# 12V_Rail.net
KiCad netlist of a schematic drawn in Altium Designer
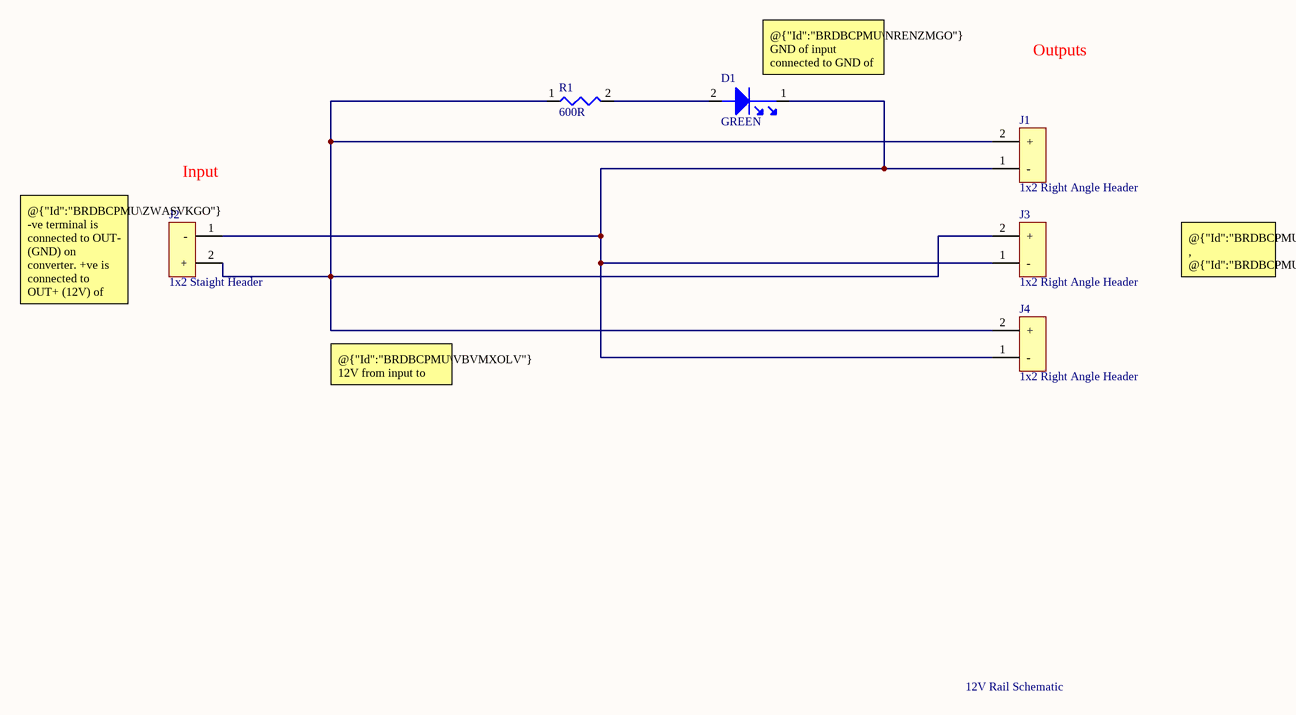
[diagram p0: 12V Rail.SchDoc]

(export (version "E")
  (design (tool "Eeschema 10.0.6"))
  (components
    (comp (ref "D1")
      (value "GREEN")
      (footprint "LED")
      (description "Green T-1 3/4 5 mm 20° Tinted 80 mcd 2.2 V Solid State LED Lamp Through Hole")
      (fields (field (name "MANUFACTURER") "Kingbright") (field (name "MANUFACTURER PART NUMBER") "WP7113GT"))
      (libsource (lib "VR Interface SchLib") (part "WP7113GT"))
    )
    (comp (ref "J1")
      (value "1x2 Right Angle Header")
      (footprint "39291028 Molex Output")
      (description "Connector Wire to Board Header 2 Position 4.2mm Solder Right Angle Thru-Hole Tray")
      (fields (field (name "MANUFACTURER") "Molex") (field (name "MANUFACTURER PART NUMBER") "39-29-1028"))
      (libsource (lib "VR Interface SchLib") (part "39-29-1028"))
    )
    (comp (ref "J2")
      (value "1x2 Staight Header")
      (footprint "39281023 Molex Input")
      (description "Connector Wire to Board Header 2 Position 4.2mm Solder Straight Thru-Hole Tray")
      (fields (field (name "MANUFACTURER") "Molex") (field (name "MANUFACTURER PART NUMBER") "39-28-1023"))
      (libsource (lib "VR Interface SchLib") (part "39-28-1023"))
    )
    (comp (ref "J3")
      (value "1x2 Right Angle Header")
      (footprint "39291028 Molex Output")
      (description "Connector Wire to Board Header 2 Position 4.2mm Solder Right Angle Thru-Hole Tray")
      (fields (field (name "MANUFACTURER") "Molex") (field (name "MANUFACTURER PART NUMBER") "39-29-1028"))
      (libsource (lib "VR Interface SchLib") (part "39-29-1028"))
    )
    (comp (ref "J4")
      (value "1x2 Right Angle Header")
      (footprint "39291028 Molex Output")
      (description "Connector Wire to Board Header 2 Position 4.2mm Solder Right Angle Thru-Hole Tray")
      (fields (field (name "MANUFACTURER") "Molex") (field (name "MANUFACTURER PART NUMBER") "39-29-1028"))
      (libsource (lib "VR Interface SchLib") (part "39-29-1028"))
    )
    (comp (ref "R1")
      (value "600R")
      (footprint "600R")
      (description "MRS25 Series Axial Thin Film Resistor 600Ohms +/-1% 0.6W +/-50ppm/degC")
      (fields
        (field (name "MANUFACTURER") "Vishay")
        (field (name "MANUFACTURER PART NUMBER") "MRS25000C6000FCT00")
      )
      (libsource (lib "VR Interface SchLib") (part "MRS25000C6000FCT00"))
    )
  )
  (nets
    (net (code "1") (name "Net-(D1-Pad2)") (class "Default")
      (node (ref "D1") (pin "2") (pinfunction "2_2") (pintype "passive"))
      (node (ref "R1") (pin "2") (pinfunction "2_2") (pintype "passive"))
    )
    (net (code "2") (name "Net-(J1-+)") (class "Default")
      (node (ref "J1") (pin "2") (pinfunction "+_2") (pintype "passive"))
      (node (ref "J2") (pin "2") (pinfunction "+_2") (pintype "passive"))
      (node (ref "J3") (pin "2") (pinfunction "+_2") (pintype "passive"))
      (node (ref "J4") (pin "2") (pinfunction "+_2") (pintype "passive"))
      (node (ref "R1") (pin "1") (pinfunction "1_1") (pintype "passive"))
    )
    (net (code "3") (name "Net-(J1--)") (class "Default")
      (node (ref "D1") (pin "1") (pinfunction "1_1") (pintype "passive"))
      (node (ref "J1") (pin "1") (pinfunction "-_1") (pintype "passive"))
      (node (ref "J2") (pin "1") (pinfunction "-_1") (pintype "passive"))
      (node (ref "J3") (pin "1") (pinfunction "-_1") (pintype "passive"))
      (node (ref "J4") (pin "1") (pinfunction "-_1") (pintype "passive"))
    )
  )
)
